# DCDC_Top.net
KiCad netlist of a schematic drawn in Altium Designer
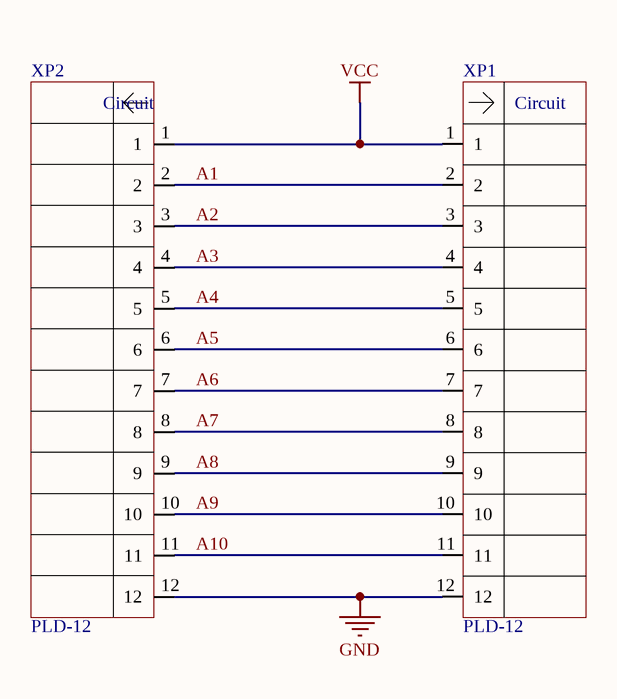
[diagram p0: DCDC_Top.SchDoc]

(export (version "E")
  (design (tool "Eeschema 10.0.6"))
  (components
    (comp (ref "XP1") (value "PLD-12") (footprint "PLD-12-3D") (libsource (lib "") (part "XP-12_1")))
    (comp (ref "XP2")
      (value "PLD-12")
      (footprint "PLD-12-3D")
      (libsource (lib "SssAccesDatbase") (part "XP-12"))
    )
  )
  (nets
    (net (code "1") (name "/A1") (class "Default")
      (node (ref "XP1") (pin "2") (pinfunction "2_2") (pintype "passive"))
      (node (ref "XP2") (pin "2") (pinfunction "2_2") (pintype "passive"))
    )
    (net (code "2") (name "/A2") (class "Default")
      (node (ref "XP1") (pin "3") (pinfunction "3_3") (pintype "passive"))
      (node (ref "XP2") (pin "3") (pinfunction "3_3") (pintype "passive"))
    )
    (net (code "3") (name "/A3") (class "Default")
      (node (ref "XP1") (pin "4") (pinfunction "4_4") (pintype "passive"))
      (node (ref "XP2") (pin "4") (pinfunction "4_4") (pintype "passive"))
    )
    (net (code "4") (name "/A4") (class "Default")
      (node (ref "XP1") (pin "5") (pinfunction "5_5") (pintype "passive"))
      (node (ref "XP2") (pin "5") (pinfunction "5_5") (pintype "passive"))
    )
    (net (code "5") (name "/A5") (class "Default")
      (node (ref "XP1") (pin "6") (pinfunction "6_6") (pintype "passive"))
      (node (ref "XP2") (pin "6") (pinfunction "6_6") (pintype "passive"))
    )
    (net (code "6") (name "/A6") (class "Default")
      (node (ref "XP1") (pin "7") (pinfunction "7_7") (pintype "passive"))
      (node (ref "XP2") (pin "7") (pinfunction "7_7") (pintype "passive"))
    )
    (net (code "7") (name "/A7") (class "Default")
      (node (ref "XP1") (pin "8") (pinfunction "8_8") (pintype "passive"))
      (node (ref "XP2") (pin "8") (pinfunction "8_8") (pintype "passive"))
    )
    (net (code "8") (name "/A8") (class "Default")
      (node (ref "XP1") (pin "9") (pinfunction "9_9") (pintype "passive"))
      (node (ref "XP2") (pin "9") (pinfunction "9_9") (pintype "passive"))
    )
    (net (code "9") (name "/A9") (class "Default")
      (node (ref "XP1") (pin "10") (pinfunction "10_10") (pintype "passive"))
      (node (ref "XP2") (pin "10") (pinfunction "10_10") (pintype "passive"))
    )
    (net (code "10") (name "/A10") (class "Default")
      (node (ref "XP1") (pin "11") (pinfunction "11_11") (pintype "passive"))
      (node (ref "XP2") (pin "11") (pinfunction "11_11") (pintype "passive"))
    )
    (net (code "11") (name "GND") (class "Default")
      (node (ref "XP1") (pin "12") (pinfunction "12_12") (pintype "passive"))
      (node (ref "XP2") (pin "12") (pinfunction "12_12") (pintype "passive"))
    )
    (net (code "12") (name "VCC") (class "Default")
      (node (ref "XP1") (pin "1") (pinfunction "1_1") (pintype "passive"))
      (node (ref "XP2") (pin "1") (pinfunction "1_1") (pintype "passive"))
    )
  )
)
